# WIFI-79.net
KiCad netlist of a schematic drawn in Altium Designer
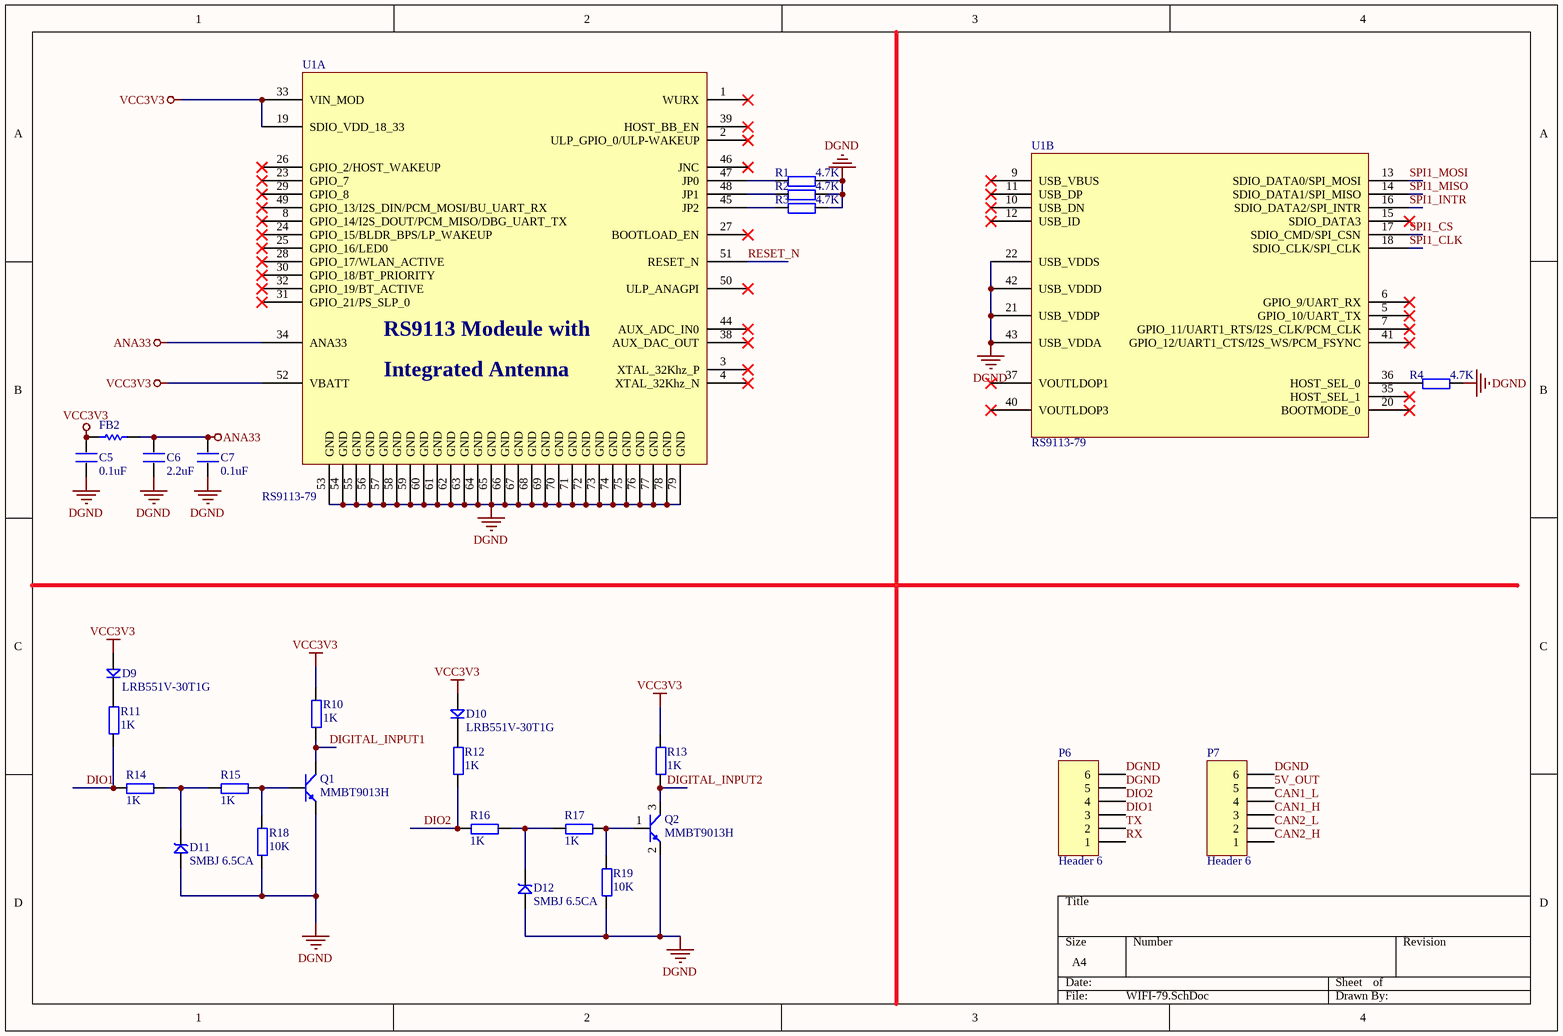
[diagram p0: WIFI-79.SchDoc]

(export (version "E")
  (design (tool "Eeschema 10.0.6"))
  (components
    (comp (ref "C5") (value "0.1uF") (footprint "0603") (libsource (lib "WARSHIP") (part "C")))
    (comp (ref "C6") (value "2.2uF") (footprint "0603") (libsource (lib "WARSHIP") (part "C")))
    (comp (ref "C7") (value "0.1uF") (footprint "0603") (libsource (lib "WARSHIP") (part "C")))
    (comp (ref "D9")
      (value "LRB551V-30T1G")
      (footprint "SOD-323")
      (libsource (lib "new") (part "D_DIODE LRB"))
    )
    (comp (ref "D10")
      (value "LRB551V-30T1G")
      (footprint "SOD-323")
      (libsource (lib "new") (part "D_DIODE LRB"))
    )
    (comp (ref "D11")
      (value "SMBJ 6.5CA")
      (footprint "DO-214AA")
      (description "TVS,SMBJ 6.5CA,600W SMD Transient Voltage Suppressor Diodes,")
      (fields (field (name "TERABITS PART NUMBER") "1D-0000001-XX"))
      (libsource (lib "new") (part "SMBJ 6.5CA"))
    )
    (comp (ref "D12")
      (value "SMBJ 6.5CA")
      (footprint "DO-214AA")
      (description "TVS,SMBJ 6.5CA,600W SMD Transient Voltage Suppressor Diodes,")
      (fields (field (name "TERABITS PART NUMBER") "1D-0000001-XX"))
      (libsource (lib "new") (part "SMBJ 6.5CA"))
    )
    (comp (ref "FB2")
      (value "BLM15EG121SN1D")
      (footprint "0603")
      (description "FILTER CHIP 120 OHM 1.5A 0402")
      (fields (field (name "PUBLISHER") "Altium Limited"))
      (libsource (lib "Miscellaneous Devices") (part "Res Semi"))
    )
    (comp (ref "P6")
      (value "Header 6")
      (footprint "P6")
      (description "接插件")
      (fields (field (name "PUBLISHER") "Altium Limited"))
      (libsource (lib "Song") (part "Header 6"))
    )
    (comp (ref "P7")
      (value "Header 6")
      (footprint "P6")
      (description "接插件")
      (fields (field (name "PUBLISHER") "Altium Limited"))
      (libsource (lib "Song") (part "Header 6"))
    )
    (comp (ref "Q1")
      (value "MMBT9013H")
      (footprint "SOT-23")
      (fields
        (field (name "TERABITS PART NUMBER") "1Q-0000001-XX")
        (field (name "MANUFACTURE PART NUMBER") "L2SC4617RT1G")
      )
      (libsource (lib "new") (part "L2SC4617RT1G"))
    )
    (comp (ref "Q2")
      (value "MMBT9013H")
      (footprint "SOT-23")
      (fields
        (field (name "TERABITS PART NUMBER") "1Q-0000001-XX")
        (field (name "MANUFACTURE PART NUMBER") "L2SC4617RT1G")
      )
      (libsource (lib "") (part "L2SC4617RT1G_1"))
    )
    (comp (ref "R1") (value "4.7K") (footprint "0603") (libsource (lib "WARSHIP") (part "R")))
    (comp (ref "R2") (value "4.7K") (footprint "0603") (libsource (lib "WARSHIP") (part "R")))
    (comp (ref "R3") (value "4.7K") (footprint "0603") (libsource (lib "WARSHIP") (part "R")))
    (comp (ref "R4") (value "4.7K") (footprint "0603") (libsource (lib "WARSHIP") (part "R")))
    (comp (ref "R10")
      (value "1K")
      (footprint "0603")
      (description "Res,1K,0603")
      (fields (field (name "TERABITS PART NUMBER") "1R-0000008-XX"))
      (libsource (lib "new") (part "R_1K"))
    )
    (comp (ref "R11")
      (value "1K")
      (footprint "0603")
      (description "Res,1K,0603")
      (libsource (lib "new") (part "R_1K"))
    )
    (comp (ref "R12")
      (value "1K")
      (footprint "0603")
      (description "Res,1K,0603")
      (libsource (lib "new") (part "R_1K"))
    )
    (comp (ref "R13")
      (value "1K")
      (footprint "0603")
      (description "Res,1K,0603")
      (fields (field (name "TERABITS PART NUMBER") "1R-0000008-XX"))
      (libsource (lib "new") (part "R_1K"))
    )
    (comp (ref "R14")
      (value "1K")
      (footprint "0603")
      (description "Res,1K,0603")
      (libsource (lib "new") (part "R_1K"))
    )
    (comp (ref "R15")
      (value "1K")
      (footprint "0603")
      (description "Res,1K,0603")
      (fields (field (name "TERABITS PART NUMBER") "1R-0000008-XX"))
      (libsource (lib "new") (part "R_1K"))
    )
    (comp (ref "R16")
      (value "1K")
      (footprint "0603")
      (description "Res,1K,0603")
      (libsource (lib "new") (part "R_1K"))
    )
    (comp (ref "R17")
      (value "1K")
      (footprint "0603")
      (description "Res,1K,0603")
      (fields (field (name "TERABITS PART NUMBER") "1R-0000008-XX"))
      (libsource (lib "new") (part "R_1K"))
    )
    (comp (ref "R18")
      (value "10K")
      (footprint "0603")
      (description "Res,1K,0603")
      (fields (field (name "TERABITS PART NUMBER") "1R-0000008-XX"))
      (libsource (lib "new") (part "R_1K"))
    )
    (comp (ref "R19")
      (value "10K")
      (footprint "0603")
      (description "Res,1K,0603")
      (fields (field (name "TERABITS PART NUMBER") "1R-0000008-XX"))
      (libsource (lib "new") (part "R_1K"))
    )
    (comp (ref "U1")
      (value "RS9113-79")
      (footprint "RS9113-79")
      (libsource (lib "Schlib1") (part "RS9113-79"))
    )
  )
  (nets
    (net (code "1") (name "/5V_OUT") (class "Default")
      (node (ref "P7") (pin "5") (pinfunction "5_5") (pintype "passive"))
    )
    (net (code "2") (name "/CAN1_H") (class "Default")
      (node (ref "P7") (pin "3") (pinfunction "3_3") (pintype "passive"))
    )
    (net (code "3") (name "/CAN1_L") (class "Default")
      (node (ref "P7") (pin "4") (pinfunction "4_4") (pintype "passive"))
    )
    (net (code "4") (name "/CAN2_H") (class "Default")
      (node (ref "P7") (pin "1") (pinfunction "1_1") (pintype "passive"))
    )
    (net (code "5") (name "/CAN2_L") (class "Default")
      (node (ref "P7") (pin "2") (pinfunction "2_2") (pintype "passive"))
    )
    (net (code "6") (name "/DIGITAL_INPUT1") (class "Default")
      (node (ref "Q1") (pin "3") (pinfunction "C_3") (pintype "passive"))
      (node (ref "R10") (pin "1") (pintype "passive"))
    )
    (net (code "7") (name "/DIGITAL_INPUT2") (class "Default")
      (node (ref "Q2") (pin "3") (pinfunction "C_3") (pintype "passive"))
      (node (ref "R13") (pin "1") (pintype "passive"))
    )
    (net (code "8") (name "/DIO1") (class "Default")
      (node (ref "P6") (pin "3") (pinfunction "3_3") (pintype "passive"))
      (node (ref "R11") (pin "1") (pintype "passive"))
      (node (ref "R14") (pin "1") (pintype "passive"))
    )
    (net (code "9") (name "/DIO2") (class "Default")
      (node (ref "P6") (pin "4") (pinfunction "4_4") (pintype "passive"))
      (node (ref "R12") (pin "1") (pintype "passive"))
      (node (ref "R16") (pin "1") (pintype "passive"))
    )
    (net (code "10") (name "/RESET_N") (class "Default")
      (node (ref "U1") (pin "51") (pinfunction "RESET_N_51") (pintype "passive"))
    )
    (net (code "11") (name "/RX") (class "Default")
      (node (ref "P6") (pin "1") (pinfunction "1_1") (pintype "passive"))
    )
    (net (code "12") (name "/SPI1_CLK") (class "Default")
      (node (ref "U1") (pin "18") (pinfunction "SDIO_CLK/SPI_CLK_18") (pintype "passive"))
    )
    (net (code "13") (name "/SPI1_CS") (class "Default")
      (node (ref "U1") (pin "17") (pinfunction "SDIO_CMD/SPI_CSN_17") (pintype "passive"))
    )
    (net (code "14") (name "/SPI1_INTR") (class "Default")
      (node (ref "U1") (pin "16") (pinfunction "SDIO_DATA2/SPI_INTR_16") (pintype "passive"))
    )
    (net (code "15") (name "/SPI1_MISO") (class "Default")
      (node (ref "U1") (pin "14") (pinfunction "SDIO_DATA1/SPI_MISO_14") (pintype "passive"))
    )
    (net (code "16") (name "/SPI1_MOSI") (class "Default")
      (node (ref "U1") (pin "13") (pinfunction "SDIO_DATA0/SPI_MOSI_13") (pintype "passive"))
    )
    (net (code "17") (name "/TX") (class "Default")
      (node (ref "P6") (pin "2") (pinfunction "2_2") (pintype "passive"))
    )
    (net (code "18") (name "ANA33") (class "Default")
      (node (ref "C6") (pin "1") (pintype "passive"))
      (node (ref "C7") (pin "1") (pintype "passive"))
      (node (ref "FB2") (pin "2") (pinfunction "2_2") (pintype "passive"))
      (node (ref "U1") (pin "34") (pinfunction "ANA33_34") (pintype "passive"))
    )
    (net (code "19") (name "DGND") (class "Default")
      (node (ref "C5") (pin "2") (pintype "passive"))
      (node (ref "C6") (pin "2") (pintype "passive"))
      (node (ref "C7") (pin "2") (pintype "passive"))
      (node (ref "D11") (pin "1") (pintype "passive"))
      (node (ref "D12") (pin "1") (pintype "passive"))
      (node (ref "P6") (pin "5") (pinfunction "5_5") (pintype "passive"))
      (node (ref "P6") (pin "6") (pinfunction "6_6") (pintype "passive"))
      (node (ref "P7") (pin "6") (pinfunction "6_6") (pintype "passive"))
      (node (ref "Q1") (pin "2") (pinfunction "E_2") (pintype "passive"))
      (node (ref "Q2") (pin "2") (pinfunction "E_2") (pintype "passive"))
      (node (ref "R1") (pin "2") (pintype "passive"))
      (node (ref "R18") (pin "1") (pintype "passive"))
      (node (ref "R19") (pin "1") (pintype "passive"))
      (node (ref "R2") (pin "2") (pintype "passive"))
      (node (ref "R3") (pin "2") (pintype "passive"))
      (node (ref "R4") (pin "2") (pintype "passive"))
      (node (ref "U1") (pin "21") (pinfunction "USB_VDDP_21") (pintype "passive"))
      (node (ref "U1") (pin "22") (pinfunction "USB_VDDS_22") (pintype "passive"))
      (node (ref "U1") (pin "42") (pinfunction "USB_VDDD_42") (pintype "passive"))
      (node (ref "U1") (pin "43") (pinfunction "USB_VDDA_43") (pintype "passive"))
      (node (ref "U1") (pin "53") (pinfunction "GND_53") (pintype "passive"))
      (node (ref "U1") (pin "54") (pinfunction "GND_54") (pintype "passive"))
      (node (ref "U1") (pin "55") (pinfunction "GND_55") (pintype "passive"))
      (node (ref "U1") (pin "56") (pinfunction "GND_56") (pintype "passive"))
      (node (ref "U1") (pin "57") (pinfunction "GND_57") (pintype "passive"))
      (node (ref "U1") (pin "58") (pinfunction "GND_58") (pintype "passive"))
      (node (ref "U1") (pin "59") (pinfunction "GND_59") (pintype "passive"))
      (node (ref "U1") (pin "60") (pinfunction "GND_60") (pintype "passive"))
      (node (ref "U1") (pin "61") (pinfunction "GND_61") (pintype "passive"))
      (node (ref "U1") (pin "62") (pinfunction "GND_62") (pintype "passive"))
      (node (ref "U1") (pin "63") (pinfunction "GND_63") (pintype "passive"))
      (node (ref "U1") (pin "64") (pinfunction "GND_64") (pintype "passive"))
      (node (ref "U1") (pin "65") (pinfunction "GND_65") (pintype "passive"))
      (node (ref "U1") (pin "66") (pinfunction "GND_66") (pintype "passive"))
      (node (ref "U1") (pin "67") (pinfunction "GND_67") (pintype "passive"))
      (node (ref "U1") (pin "68") (pinfunction "GND_68") (pintype "passive"))
      (node (ref "U1") (pin "69") (pinfunction "GND_69") (pintype "passive"))
      (node (ref "U1") (pin "70") (pinfunction "GND_70") (pintype "passive"))
      (node (ref "U1") (pin "71") (pinfunction "GND_71") (pintype "passive"))
      (node (ref "U1") (pin "72") (pinfunction "GND_72") (pintype "passive"))
      (node (ref "U1") (pin "73") (pinfunction "GND_73") (pintype "passive"))
      (node (ref "U1") (pin "74") (pinfunction "GND_74") (pintype "passive"))
      (node (ref "U1") (pin "75") (pinfunction "GND_75") (pintype "passive"))
      (node (ref "U1") (pin "76") (pinfunction "GND_76") (pintype "passive"))
      (node (ref "U1") (pin "77") (pinfunction "GND_77") (pintype "passive"))
      (node (ref "U1") (pin "78") (pinfunction "GND_78") (pintype "passive"))
      (node (ref "U1") (pin "79") (pinfunction "GND_79") (pintype "passive"))
    )
    (net (code "20") (name "Net-(D9-Pad1)") (class "Default")
      (node (ref "D9") (pin "1") (pintype "passive"))
      (node (ref "R11") (pin "2") (pintype "passive"))
    )
    (net (code "21") (name "Net-(D10-Pad1)") (class "Default")
      (node (ref "D10") (pin "1") (pintype "passive"))
      (node (ref "R12") (pin "2") (pintype "passive"))
    )
    (net (code "22") (name "Net-(D11-Pad2)") (class "Default")
      (node (ref "D11") (pin "2") (pintype "passive"))
      (node (ref "R14") (pin "2") (pintype "passive"))
      (node (ref "R15") (pin "1") (pintype "passive"))
    )
    (net (code "23") (name "Net-(D12-Pad2)") (class "Default")
      (node (ref "D12") (pin "2") (pintype "passive"))
      (node (ref "R16") (pin "2") (pintype "passive"))
      (node (ref "R17") (pin "1") (pintype "passive"))
    )
    (net (code "24") (name "Net-(Q1-B)") (class "Default")
      (node (ref "Q1") (pin "1") (pinfunction "B_1") (pintype "passive"))
      (node (ref "R15") (pin "2") (pintype "passive"))
      (node (ref "R18") (pin "2") (pintype "passive"))
    )
    (net (code "25") (name "Net-(Q2-B)") (class "Default")
      (node (ref "Q2") (pin "1") (pinfunction "B_1") (pintype "passive"))
      (node (ref "R17") (pin "2") (pintype "passive"))
      (node (ref "R19") (pin "2") (pintype "passive"))
    )
    (net (code "26") (name "Net-(U1A-JP0)") (class "Default")
      (node (ref "R1") (pin "1") (pintype "passive"))
      (node (ref "U1") (pin "47") (pinfunction "JP0_47") (pintype "passive"))
    )
    (net (code "27") (name "Net-(U1A-JP1)") (class "Default")
      (node (ref "R2") (pin "1") (pintype "passive"))
      (node (ref "U1") (pin "48") (pinfunction "JP1_48") (pintype "passive"))
    )
    (net (code "28") (name "Net-(U1A-JP2)") (class "Default")
      (node (ref "R3") (pin "1") (pintype "passive"))
      (node (ref "U1") (pin "45") (pinfunction "JP2_45") (pintype "passive"))
    )
    (net (code "29") (name "Net-(U1B-HOST_SEL_0)") (class "Default")
      (node (ref "R4") (pin "1") (pintype "passive"))
      (node (ref "U1") (pin "36") (pinfunction "HOST_SEL_0_36") (pintype "passive"))
    )
    (net (code "30") (name "VCC3V3") (class "Default")
      (node (ref "C5") (pin "1") (pintype "passive"))
      (node (ref "D10") (pin "2") (pintype "passive"))
      (node (ref "D9") (pin "2") (pintype "passive"))
      (node (ref "FB2") (pin "1") (pinfunction "1_1") (pintype "passive"))
      (node (ref "R10") (pin "2") (pintype "passive"))
      (node (ref "R13") (pin "2") (pintype "passive"))
      (node (ref "U1") (pin "19") (pinfunction "SDIO_VDD_18_33_19") (pintype "passive"))
      (node (ref "U1") (pin "33") (pinfunction "VIN_MOD_33") (pintype "passive"))
      (node (ref "U1") (pin "52") (pinfunction "VBATT_52") (pintype "passive"))
    )
    (net (code "31") (name "unconnected-(U1A-AUX_ADC_IN0-Pad44)") (class "Default")
      (node (ref "U1") (pin "44") (pinfunction "AUX_ADC_IN0_44") (pintype "passive+no_connect"))
    )
    (net (code "32") (name "unconnected-(U1A-AUX_DAC_OUT-Pad38)") (class "Default")
      (node (ref "U1") (pin "38") (pinfunction "AUX_DAC_OUT_38") (pintype "passive+no_connect"))
    )
    (net (code "33") (name "unconnected-(U1A-BOOTLOAD_EN-Pad27)") (class "Default")
      (node (ref "U1") (pin "27") (pinfunction "BOOTLOAD_EN_27") (pintype "passive+no_connect"))
    )
    (net (code "34") (name "unconnected-(U1A-GPIO_2{slash}HOST_WAKEUP-Pad26)") (class "Default")
      (node (ref "U1") (pin "26") (pinfunction "GPIO_2/HOST_WAKEUP_26") (pintype "passive+no_connect"))
    )
    (net (code "35") (name "unconnected-(U1A-GPIO_7-Pad23)") (class "Default")
      (node (ref "U1") (pin "23") (pinfunction "GPIO_7_23") (pintype "passive+no_connect"))
    )
    (net (code "36") (name "unconnected-(U1A-GPIO_8-Pad29)") (class "Default")
      (node (ref "U1") (pin "29") (pinfunction "GPIO_8_29") (pintype "passive+no_connect"))
    )
    (net (code "37") (name "unconnected-(U1A-GPIO_13{slash}I2S_DIN{slash}PCM_MOSI{slash}BU_UART_RX-Pad49)") (class "Default")
      (node (ref "U1") (pin "49") (pinfunction "GPIO_13/I2S_DIN/PCM_MOSI/BU_UART_RX_49") (pintype "passive+no_connect"))
    )
    (net (code "38") (name "unconnected-(U1A-GPIO_14{slash}I2S_DOUT{slash}PCM_MISO{slash}DBG_UART_TX-Pad8)") (class "Default")
      (node (ref "U1") (pin "8") (pinfunction "GPIO_14/I2S_DOUT/PCM_MISO/DBG_UART_TX_8") (pintype "passive+no_connect"))
    )
    (net (code "39") (name "unconnected-(U1A-GPIO_15{slash}BLDR_BPS{slash}LP_WAKEUP-Pad24)") (class "Default")
      (node (ref "U1") (pin "24") (pinfunction "GPIO_15/BLDR_BPS/LP_WAKEUP_24") (pintype "passive+no_connect"))
    )
    (net (code "40") (name "unconnected-(U1A-GPIO_16{slash}LED0-Pad25)") (class "Default")
      (node (ref "U1") (pin "25") (pinfunction "GPIO_16/LED0_25") (pintype "passive+no_connect"))
    )
    (net (code "41") (name "unconnected-(U1A-GPIO_17{slash}WLAN_ACTIVE-Pad28)") (class "Default")
      (node (ref "U1") (pin "28") (pinfunction "GPIO_17/WLAN_ACTIVE_28") (pintype "passive+no_connect"))
    )
    (net (code "42") (name "unconnected-(U1A-GPIO_18{slash}BT_PRIORITY-Pad30)") (class "Default")
      (node (ref "U1") (pin "30") (pinfunction "GPIO_18/BT_PRIORITY_30") (pintype "passive+no_connect"))
    )
    (net (code "43") (name "unconnected-(U1A-GPIO_19{slash}BT_ACTIVE-Pad32)") (class "Default")
      (node (ref "U1") (pin "32") (pinfunction "GPIO_19/BT_ACTIVE_32") (pintype "passive+no_connect"))
    )
    (net (code "44") (name "unconnected-(U1A-GPIO_21{slash}PS_SLP_0-Pad31)") (class "Default")
      (node (ref "U1") (pin "31") (pinfunction "GPIO_21/PS_SLP_0_31") (pintype "passive+no_connect"))
    )
    (net (code "45") (name "unconnected-(U1A-HOST_BB_EN-Pad39)") (class "Default")
      (node (ref "U1") (pin "39") (pinfunction "HOST_BB_EN_39") (pintype "passive+no_connect"))
    )
    (net (code "46") (name "unconnected-(U1A-JNC-Pad46)") (class "Default")
      (node (ref "U1") (pin "46") (pinfunction "JNC_46") (pintype "passive+no_connect"))
    )
    (net (code "47") (name "unconnected-(U1A-ULP_ANAGPI-Pad50)") (class "Default")
      (node (ref "U1") (pin "50") (pinfunction "ULP_ANAGPI_50") (pintype "passive+no_connect"))
    )
    (net (code "48") (name "unconnected-(U1A-ULP_GPIO_0{slash}ULP-WAKEUP-Pad2)") (class "Default")
      (node (ref "U1") (pin "2") (pinfunction "ULP_GPIO_0/ULP-WAKEUP_2") (pintype "passive+no_connect"))
    )
    (net (code "49") (name "unconnected-(U1A-WURX-Pad1)") (class "Default")
      (node (ref "U1") (pin "1") (pinfunction "WURX_1") (pintype "passive+no_connect"))
    )
    (net (code "50") (name "unconnected-(U1A-XTAL_32Khz_N-Pad4)") (class "Default")
      (node (ref "U1") (pin "4") (pinfunction "XTAL_32Khz_N_4") (pintype "passive+no_connect"))
    )
    (net (code "51") (name "unconnected-(U1A-XTAL_32Khz_P-Pad3)") (class "Default")
      (node (ref "U1") (pin "3") (pinfunction "XTAL_32Khz_P_3") (pintype "passive+no_connect"))
    )
    (net (code "52") (name "unconnected-(U1B-BOOTMODE_0-Pad20)") (class "Default")
      (node (ref "U1") (pin "20") (pinfunction "BOOTMODE_0_20") (pintype "passive+no_connect"))
    )
    (net (code "53") (name "unconnected-(U1B-GPIO_9{slash}UART_RX-Pad6)") (class "Default")
      (node (ref "U1") (pin "6") (pinfunction "GPIO_9/UART_RX_6") (pintype "passive+no_connect"))
    )
    (net (code "54") (name "unconnected-(U1B-GPIO_10{slash}UART_TX-Pad5)") (class "Default")
      (node (ref "U1") (pin "5") (pinfunction "GPIO_10/UART_TX_5") (pintype "passive+no_connect"))
    )
    (net (code "55") (name "unconnected-(U1B-GPIO_11{slash}UART1_RTS{slash}I2S_CLK{slash}PCM_CLK-Pad7)") (class "Default")
      (node (ref "U1") (pin "7") (pinfunction "GPIO_11/UART1_RTS/I2S_CLK/PCM_CLK_7") (pintype "passive+no_connect"))
    )
    (net (code "56") (name "unconnected-(U1B-GPIO_12{slash}UART1_CTS{slash}I2S_WS{slash}PCM_FSYNC-Pad41)") (class "Default")
      (node (ref "U1") (pin "41") (pinfunction "GPIO_12/UART1_CTS/I2S_WS/PCM_FSYNC_41") (pintype "passive+no_connect"))
    )
    (net (code "57") (name "unconnected-(U1B-HOST_SEL_1-Pad35)") (class "Default")
      (node (ref "U1") (pin "35") (pinfunction "HOST_SEL_1_35") (pintype "passive+no_connect"))
    )
    (net (code "58") (name "unconnected-(U1B-SDIO_DATA3-Pad15)") (class "Default")
      (node (ref "U1") (pin "15") (pinfunction "SDIO_DATA3_15") (pintype "passive+no_connect"))
    )
    (net (code "59") (name "unconnected-(U1B-USB_DN-Pad10)") (class "Default")
      (node (ref "U1") (pin "10") (pinfunction "USB_DN_10") (pintype "passive+no_connect"))
    )
    (net (code "60") (name "unconnected-(U1B-USB_DP-Pad11)") (class "Default")
      (node (ref "U1") (pin "11") (pinfunction "USB_DP_11") (pintype "passive+no_connect"))
    )
    (net (code "61") (name "unconnected-(U1B-USB_ID-Pad12)") (class "Default")
      (node (ref "U1") (pin "12") (pinfunction "USB_ID_12") (pintype "passive+no_connect"))
    )
    (net (code "62") (name "unconnected-(U1B-USB_VBUS-Pad9)") (class "Default")
      (node (ref "U1") (pin "9") (pinfunction "USB_VBUS_9") (pintype "passive+no_connect"))
    )
    (net (code "63") (name "unconnected-(U1B-VOUTLDOP1-Pad37)") (class "Default")
      (node (ref "U1") (pin "37") (pinfunction "VOUTLDOP1_37") (pintype "passive+no_connect"))
    )
    (net (code "64") (name "unconnected-(U1B-VOUTLDOP3-Pad40)") (class "Default")
      (node (ref "U1") (pin "40") (pinfunction "VOUTLDOP3_40") (pintype "passive+no_connect"))
    )
  )
)
